# HexBoard.net
KiCad netlist of a schematic drawn in EAGLE
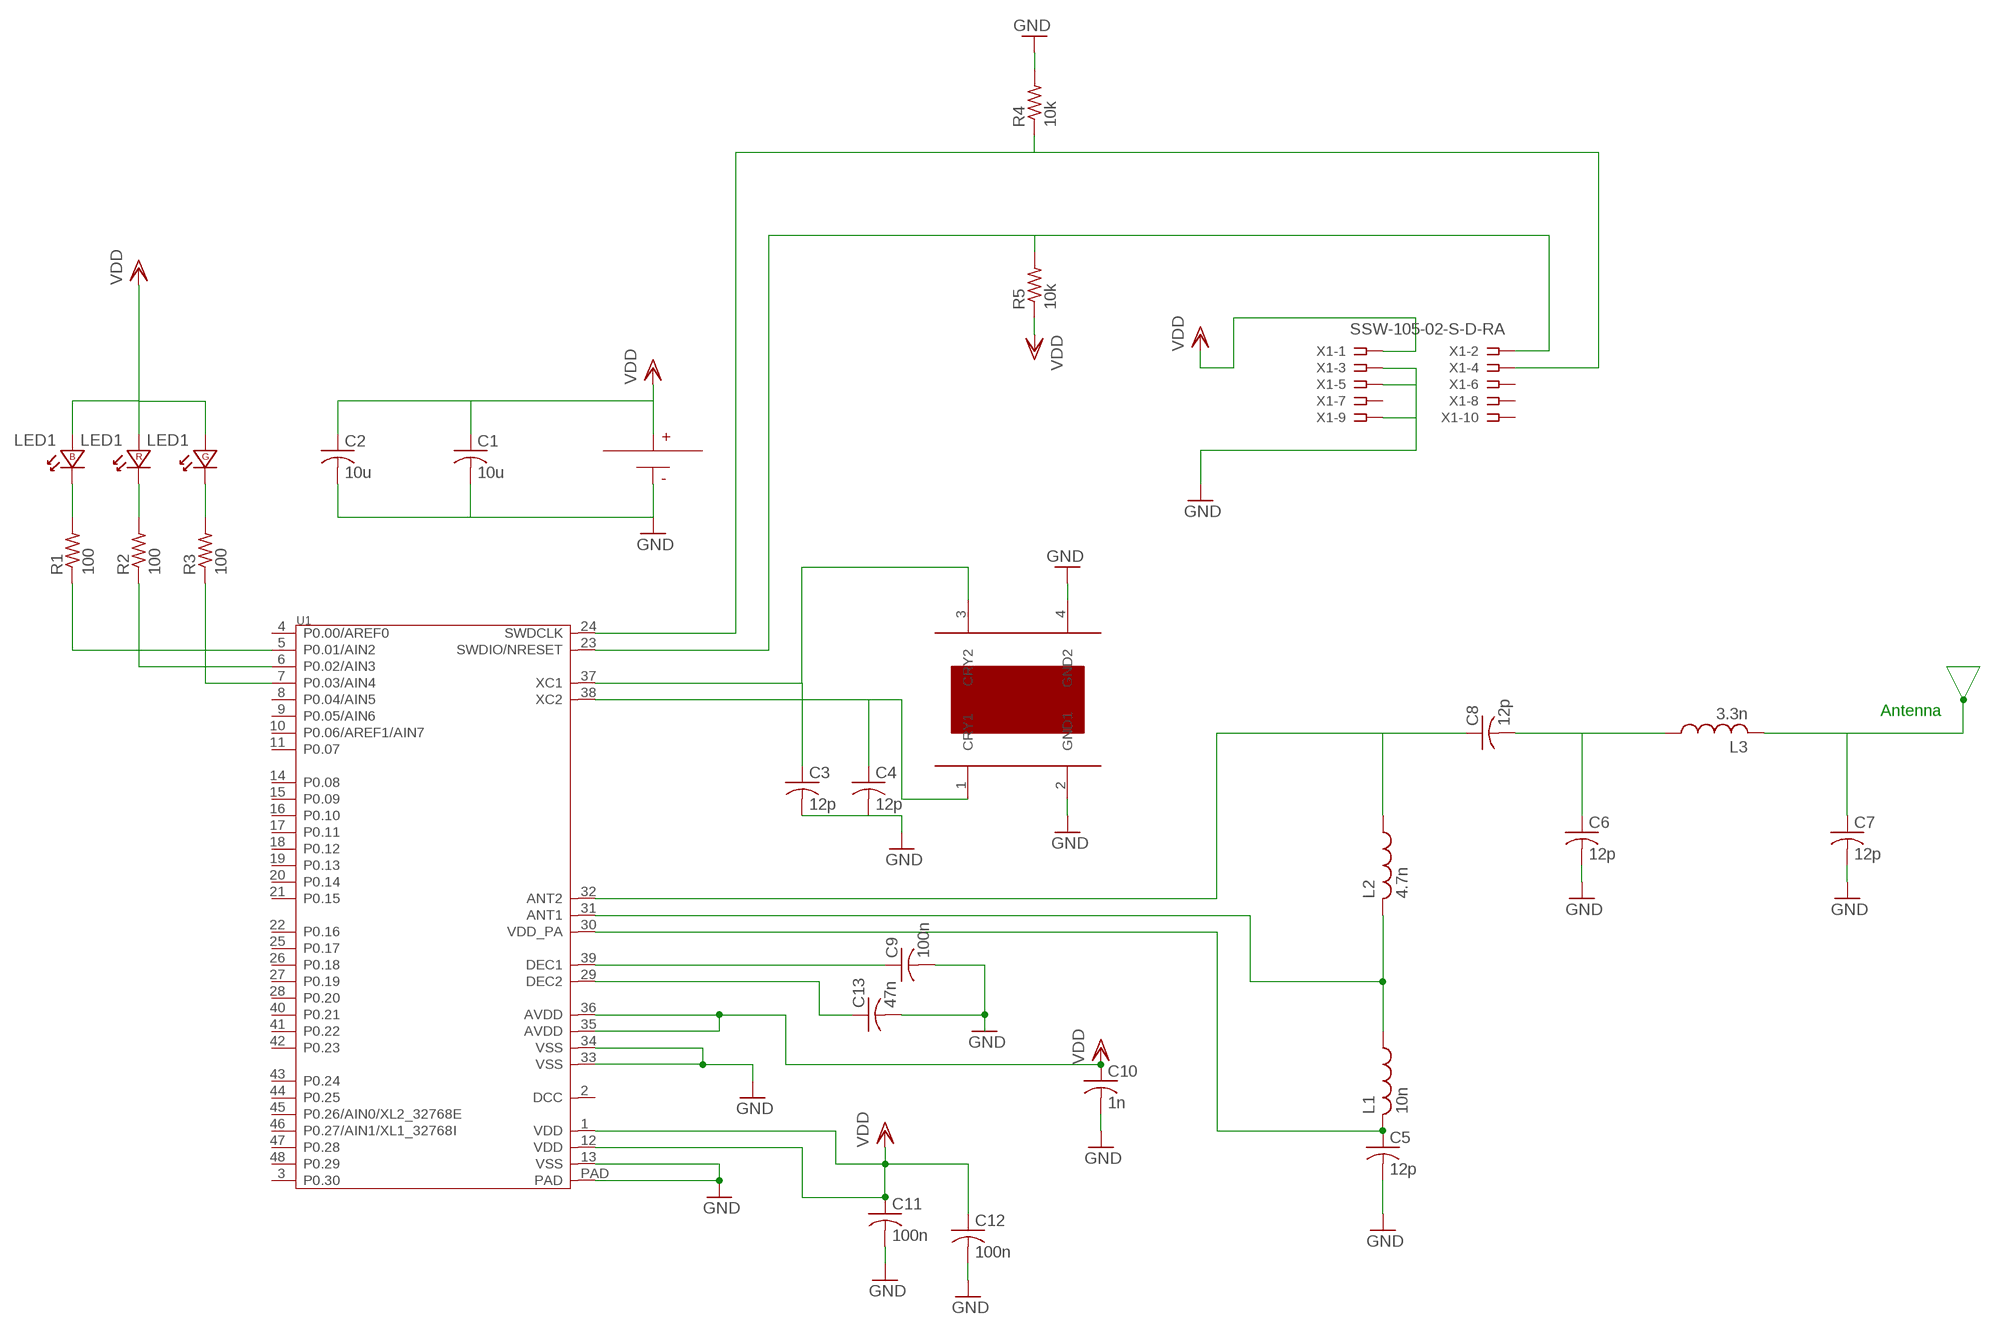
[diagram p0: schematic, sheet 1]

(export (version "E")
  (design (tool "Eeschema 10.0.6"))
  (components
    (comp (ref "B1")
      (value "CON-COINCEL-HOLDER-KEYSTONE-3012TR")
      (footprint "eagle-import:16MM-COINCELL-KEYSTONE")
      (libsource (lib "eagle-import") (part "CON-COINCEL-HOLDER-KEYSTONE-3012TR"))
    )
    (comp (ref "C1")
      (value "10u")
      (footprint "eagle-import:C0805K")
      (libsource (lib "eagle-import") (part "C-USC0805K"))
    )
    (comp (ref "C2")
      (value "10u")
      (footprint "eagle-import:C0805K")
      (libsource (lib "eagle-import") (part "C-USC0805K"))
    )
    (comp (ref "C3")
      (value "12p")
      (footprint "eagle-import:C0402")
      (libsource (lib "eagle-import") (part "C-USC0402"))
    )
    (comp (ref "C4")
      (value "12p")
      (footprint "eagle-import:C0402")
      (libsource (lib "eagle-import") (part "C-USC0402"))
    )
    (comp (ref "C5")
      (value "12p")
      (footprint "eagle-import:C0402")
      (libsource (lib "eagle-import") (part "C-USC0402"))
    )
    (comp (ref "C6")
      (value "12p")
      (footprint "eagle-import:C0402")
      (libsource (lib "eagle-import") (part "C-USC0402"))
    )
    (comp (ref "C7")
      (value "12p")
      (footprint "eagle-import:C0402")
      (libsource (lib "eagle-import") (part "C-USC0402"))
    )
    (comp (ref "C8")
      (value "12p")
      (footprint "eagle-import:C0402")
      (libsource (lib "eagle-import") (part "C-USC0402"))
    )
    (comp (ref "C9")
      (value "100n")
      (footprint "eagle-import:C0402")
      (libsource (lib "eagle-import") (part "C-USC0402"))
    )
    (comp (ref "C10")
      (value "1n")
      (footprint "eagle-import:C0402")
      (libsource (lib "eagle-import") (part "C-USC0402"))
    )
    (comp (ref "C11")
      (value "100n")
      (footprint "eagle-import:C0402")
      (libsource (lib "eagle-import") (part "C-USC0402"))
    )
    (comp (ref "C12")
      (value "100n")
      (footprint "eagle-import:C0402")
      (libsource (lib "eagle-import") (part "C-USC0402"))
    )
    (comp (ref "C13")
      (value "47n")
      (footprint "eagle-import:C0603K")
      (libsource (lib "eagle-import") (part "C-USC0603K"))
    )
    (comp (ref "L1")
      (value "10n")
      (footprint "eagle-import:CHIP_INDUCTOR")
      (libsource (lib "eagle-import") (part "402_CHIP_INDUCTOR"))
    )
    (comp (ref "L2")
      (value "4.7n")
      (footprint "eagle-import:CHIP_INDUCTOR")
      (libsource (lib "eagle-import") (part "402_CHIP_INDUCTOR"))
    )
    (comp (ref "L3")
      (value "3.3n")
      (footprint "eagle-import:CHIP_INDUCTOR")
      (libsource (lib "eagle-import") (part "402_CHIP_INDUCTOR"))
    )
    (comp (ref "LED1")
      (value "LED-RGB-SEPARATE-3528")
      (footprint "eagle-import:LED-3528")
      (libsource (lib "eagle-import") (part "LED-RGB-SEPARATE-3528"))
    )
    (comp (ref "R1")
      (value "100")
      (footprint "eagle-import:R0402")
      (libsource (lib "eagle-import") (part "R-US_R0402"))
    )
    (comp (ref "R2")
      (value "100")
      (footprint "eagle-import:R0402")
      (libsource (lib "eagle-import") (part "R-US_R0402"))
    )
    (comp (ref "R3")
      (value "100")
      (footprint "eagle-import:R0402")
      (libsource (lib "eagle-import") (part "R-US_R0402"))
    )
    (comp (ref "R4")
      (value "10k")
      (footprint "eagle-import:R0402")
      (libsource (lib "eagle-import") (part "R-US_R0402"))
    )
    (comp (ref "R5")
      (value "10k")
      (footprint "eagle-import:R0402")
      (libsource (lib "eagle-import") (part "R-US_R0402"))
    )
    (comp (ref "U$1")
      (value "TXC-CRYSTAL")
      (footprint "eagle-import:TXC_CRYSTAL")
      (libsource (lib "eagle-import") (part "TXC-CRYSTAL"))
    )
    (comp (ref "U1")
      (value "NRF51822")
      (footprint "eagle-import:QFN48-6X6MM")
      (libsource (lib "eagle-import") (part "NRF51822"))
    )
    (comp (ref "X1")
      (value "SSW-105-02-S-D-RA")
      (footprint "eagle-import:TSW-105-02-S-D-RA")
      (libsource (lib "eagle-import") (part "SSW-105-02-S-D-RA"))
    )
  )
  (nets
    (net (code "1") (name "GND") (class "Default")
      (node (ref "B1") (pin "NEG") (pinfunction "NEG_NEG") (pintype "power_in"))
      (node (ref "C1") (pin "2") (pinfunction "2_2") (pintype "passive"))
      (node (ref "C10") (pin "2") (pinfunction "2_2") (pintype "passive"))
      (node (ref "C11") (pin "2") (pinfunction "2_2") (pintype "passive"))
      (node (ref "C12") (pin "2") (pinfunction "2_2") (pintype "passive"))
      (node (ref "C13") (pin "2") (pinfunction "2_2") (pintype "passive"))
      (node (ref "C2") (pin "2") (pinfunction "2_2") (pintype "passive"))
      (node (ref "C3") (pin "2") (pinfunction "2_2") (pintype "passive"))
      (node (ref "C4") (pin "2") (pinfunction "2_2") (pintype "passive"))
      (node (ref "C5") (pin "2") (pinfunction "2_2") (pintype "passive"))
      (node (ref "C6") (pin "2") (pinfunction "2_2") (pintype "passive"))
      (node (ref "C7") (pin "2") (pinfunction "2_2") (pintype "passive"))
      (node (ref "C9") (pin "2") (pinfunction "2_2") (pintype "passive"))
      (node (ref "R4") (pin "2") (pinfunction "2_2") (pintype "passive"))
      (node (ref "U$1") (pin "2") (pinfunction "GND1_2") (pintype "bidirectional"))
      (node (ref "U$1") (pin "4") (pinfunction "GND2_4") (pintype "bidirectional"))
      (node (ref "U1") (pin "13") (pinfunction "VSS_13") (pintype "bidirectional"))
      (node (ref "U1") (pin "33") (pinfunction "VSS_33") (pintype "bidirectional"))
      (node (ref "U1") (pin "34") (pinfunction "VSS_34") (pintype "bidirectional"))
      (node (ref "U1") (pin "PAD") (pinfunction "PAD_PAD") (pintype "bidirectional"))
      (node (ref "X1") (pin "3") (pinfunction "1_3") (pintype "passive"))
      (node (ref "X1") (pin "5") (pinfunction "1_5") (pintype "passive"))
      (node (ref "X1") (pin "9") (pinfunction "1_9") (pintype "passive"))
    )
    (net (code "2") (name "Net-(C6-Pad1)") (class "Default")
      (node (ref "C6") (pin "1") (pinfunction "1_1") (pintype "passive"))
      (node (ref "C8") (pin "2") (pinfunction "2_2") (pintype "passive"))
      (node (ref "L3") (pin "1") (pinfunction "1_1") (pintype "passive"))
    )
    (net (code "3") (name "Net-(C7-Pad1)") (class "Default")
      (node (ref "C7") (pin "1") (pinfunction "1_1") (pintype "passive"))
      (node (ref "L3") (pin "2") (pinfunction "2_2") (pintype "passive"))
    )
    (net (code "4") (name "Net-(LED1A-K)") (class "Default")
      (node (ref "LED1") (pin "6") (pinfunction "K_6") (pintype "passive"))
      (node (ref "R1") (pin "2") (pinfunction "2_2") (pintype "passive"))
    )
    (net (code "5") (name "Net-(LED1B-K)") (class "Default")
      (node (ref "LED1") (pin "4") (pinfunction "K_4") (pintype "passive"))
      (node (ref "R3") (pin "2") (pinfunction "2_2") (pintype "passive"))
    )
    (net (code "6") (name "Net-(LED1C-K)") (class "Default")
      (node (ref "LED1") (pin "5") (pinfunction "K_5") (pintype "passive"))
      (node (ref "R2") (pin "2") (pinfunction "2_2") (pintype "passive"))
    )
    (net (code "7") (name "Net-(U$1-CRY1)") (class "Default")
      (node (ref "C4") (pin "1") (pinfunction "1_1") (pintype "passive"))
      (node (ref "U$1") (pin "1") (pinfunction "CRY1_1") (pintype "bidirectional"))
      (node (ref "U1") (pin "38") (pinfunction "XC2_38") (pintype "bidirectional"))
    )
    (net (code "8") (name "Net-(U$1-CRY2)") (class "Default")
      (node (ref "C3") (pin "1") (pinfunction "1_1") (pintype "passive"))
      (node (ref "U$1") (pin "3") (pinfunction "CRY2_3") (pintype "bidirectional"))
      (node (ref "U1") (pin "37") (pinfunction "XC1_37") (pintype "bidirectional"))
    )
    (net (code "9") (name "Net-(U1-ANT1)") (class "Default")
      (node (ref "L1") (pin "1") (pinfunction "1_1") (pintype "passive"))
      (node (ref "L2") (pin "2") (pinfunction "2_2") (pintype "passive"))
      (node (ref "U1") (pin "31") (pinfunction "ANT1_31") (pintype "bidirectional"))
    )
    (net (code "10") (name "Net-(U1-ANT2)") (class "Default")
      (node (ref "C8") (pin "1") (pinfunction "1_1") (pintype "passive"))
      (node (ref "L2") (pin "1") (pinfunction "1_1") (pintype "passive"))
      (node (ref "U1") (pin "32") (pinfunction "ANT2_32") (pintype "bidirectional"))
    )
    (net (code "11") (name "Net-(U1-DEC1)") (class "Default")
      (node (ref "C9") (pin "1") (pinfunction "1_1") (pintype "passive"))
      (node (ref "U1") (pin "39") (pinfunction "DEC1_39") (pintype "bidirectional"))
    )
    (net (code "12") (name "Net-(U1-DEC2)") (class "Default")
      (node (ref "C13") (pin "1") (pinfunction "1_1") (pintype "passive"))
      (node (ref "U1") (pin "29") (pinfunction "DEC2_29") (pintype "bidirectional"))
    )
    (net (code "13") (name "Net-(U1-P0.01{slash}AIN2)") (class "Default")
      (node (ref "R1") (pin "1") (pinfunction "1_1") (pintype "passive"))
      (node (ref "U1") (pin "5") (pinfunction "P0.01/AIN2_5") (pintype "bidirectional"))
    )
    (net (code "14") (name "Net-(U1-P0.02{slash}AIN3)") (class "Default")
      (node (ref "R2") (pin "1") (pinfunction "1_1") (pintype "passive"))
      (node (ref "U1") (pin "6") (pinfunction "P0.02/AIN3_6") (pintype "bidirectional"))
    )
    (net (code "15") (name "Net-(U1-P0.03{slash}AIN4)") (class "Default")
      (node (ref "R3") (pin "1") (pinfunction "1_1") (pintype "passive"))
      (node (ref "U1") (pin "7") (pinfunction "P0.03/AIN4_7") (pintype "bidirectional"))
    )
    (net (code "16") (name "Net-(U1-SWDCLK)") (class "Default")
      (node (ref "R4") (pin "1") (pinfunction "1_1") (pintype "passive"))
      (node (ref "U1") (pin "24") (pinfunction "SWDCLK_24") (pintype "bidirectional"))
      (node (ref "X1") (pin "4") (pinfunction "1_4") (pintype "passive"))
    )
    (net (code "17") (name "Net-(U1-SWDIO{slash}NRESET)") (class "Default")
      (node (ref "R5") (pin "2") (pinfunction "2_2") (pintype "passive"))
      (node (ref "U1") (pin "23") (pinfunction "SWDIO/NRESET_23") (pintype "bidirectional"))
      (node (ref "X1") (pin "2") (pinfunction "1_2") (pintype "passive"))
    )
    (net (code "18") (name "Net-(U1-VDD_PA)") (class "Default")
      (node (ref "C5") (pin "1") (pinfunction "1_1") (pintype "passive"))
      (node (ref "L1") (pin "2") (pinfunction "2_2") (pintype "passive"))
      (node (ref "U1") (pin "30") (pinfunction "VDD_PA_30") (pintype "bidirectional"))
    )
    (net (code "19") (name "VDD") (class "Default")
      (node (ref "B1") (pin "POS@1") (pinfunction "POS_POS@1") (pintype "power_in"))
      (node (ref "B1") (pin "POS@2") (pinfunction "POS_POS@2") (pintype "power_in"))
      (node (ref "C1") (pin "1") (pinfunction "1_1") (pintype "passive"))
      (node (ref "C10") (pin "1") (pinfunction "1_1") (pintype "passive"))
      (node (ref "C11") (pin "1") (pinfunction "1_1") (pintype "passive"))
      (node (ref "C12") (pin "1") (pinfunction "1_1") (pintype "passive"))
      (node (ref "C2") (pin "1") (pinfunction "1_1") (pintype "passive"))
      (node (ref "LED1") (pin "1") (pinfunction "A_1") (pintype "passive"))
      (node (ref "LED1") (pin "2") (pinfunction "A_2") (pintype "passive"))
      (node (ref "LED1") (pin "3") (pinfunction "A_3") (pintype "passive"))
      (node (ref "R5") (pin "1") (pinfunction "1_1") (pintype "passive"))
      (node (ref "U1") (pin "1") (pinfunction "VDD_1") (pintype "bidirectional"))
      (node (ref "U1") (pin "12") (pinfunction "VDD_12") (pintype "bidirectional"))
      (node (ref "U1") (pin "35") (pinfunction "AVDD_35") (pintype "bidirectional"))
      (node (ref "U1") (pin "36") (pinfunction "AVDD_36") (pintype "bidirectional"))
      (node (ref "X1") (pin "1") (pinfunction "1_1") (pintype "passive"))
    )
    (net (code "20") (name "unconnected-(U1-DCC-Pad2)") (class "Default")
      (node (ref "U1") (pin "2") (pinfunction "DCC_2") (pintype "bidirectional"))
    )
    (net (code "21") (name "unconnected-(U1-P0.00{slash}AREF0-Pad4)") (class "Default")
      (node (ref "U1") (pin "4") (pinfunction "P0.00/AREF0_4") (pintype "bidirectional"))
    )
    (net (code "22") (name "unconnected-(U1-P0.04{slash}AIN5-Pad8)") (class "Default")
      (node (ref "U1") (pin "8") (pinfunction "P0.04/AIN5_8") (pintype "bidirectional"))
    )
    (net (code "23") (name "unconnected-(U1-P0.05{slash}AIN6-Pad9)") (class "Default")
      (node (ref "U1") (pin "9") (pinfunction "P0.05/AIN6_9") (pintype "bidirectional"))
    )
    (net (code "24") (name "unconnected-(U1-P0.06{slash}AREF1{slash}AIN7-Pad10)") (class "Default")
      (node (ref "U1") (pin "10") (pinfunction "P0.06/AREF1/AIN7_10") (pintype "bidirectional"))
    )
    (net (code "25") (name "unconnected-(U1-P0.07-Pad11)") (class "Default")
      (node (ref "U1") (pin "11") (pinfunction "P0.07_11") (pintype "bidirectional"))
    )
    (net (code "26") (name "unconnected-(U1-P0.08-Pad14)") (class "Default")
      (node (ref "U1") (pin "14") (pinfunction "P0.08_14") (pintype "bidirectional"))
    )
    (net (code "27") (name "unconnected-(U1-P0.09-Pad15)") (class "Default")
      (node (ref "U1") (pin "15") (pinfunction "P0.09_15") (pintype "bidirectional"))
    )
    (net (code "28") (name "unconnected-(U1-P0.10-Pad16)") (class "Default")
      (node (ref "U1") (pin "16") (pinfunction "P0.10_16") (pintype "bidirectional"))
    )
    (net (code "29") (name "unconnected-(U1-P0.11-Pad17)") (class "Default")
      (node (ref "U1") (pin "17") (pinfunction "P0.11_17") (pintype "bidirectional"))
    )
    (net (code "30") (name "unconnected-(U1-P0.12-Pad18)") (class "Default")
      (node (ref "U1") (pin "18") (pinfunction "P0.12_18") (pintype "bidirectional"))
    )
    (net (code "31") (name "unconnected-(U1-P0.13-Pad19)") (class "Default")
      (node (ref "U1") (pin "19") (pinfunction "P0.13_19") (pintype "bidirectional"))
    )
    (net (code "32") (name "unconnected-(U1-P0.14-Pad20)") (class "Default")
      (node (ref "U1") (pin "20") (pinfunction "P0.14_20") (pintype "bidirectional"))
    )
    (net (code "33") (name "unconnected-(U1-P0.15-Pad21)") (class "Default")
      (node (ref "U1") (pin "21") (pinfunction "P0.15_21") (pintype "bidirectional"))
    )
    (net (code "34") (name "unconnected-(U1-P0.16-Pad22)") (class "Default")
      (node (ref "U1") (pin "22") (pinfunction "P0.16_22") (pintype "bidirectional"))
    )
    (net (code "35") (name "unconnected-(U1-P0.17-Pad25)") (class "Default")
      (node (ref "U1") (pin "25") (pinfunction "P0.17_25") (pintype "bidirectional"))
    )
    (net (code "36") (name "unconnected-(U1-P0.18-Pad26)") (class "Default")
      (node (ref "U1") (pin "26") (pinfunction "P0.18_26") (pintype "bidirectional"))
    )
    (net (code "37") (name "unconnected-(U1-P0.19-Pad27)") (class "Default")
      (node (ref "U1") (pin "27") (pinfunction "P0.19_27") (pintype "bidirectional"))
    )
    (net (code "38") (name "unconnected-(U1-P0.20-Pad28)") (class "Default")
      (node (ref "U1") (pin "28") (pinfunction "P0.20_28") (pintype "bidirectional"))
    )
    (net (code "39") (name "unconnected-(U1-P0.21-Pad40)") (class "Default")
      (node (ref "U1") (pin "40") (pinfunction "P0.21_40") (pintype "bidirectional"))
    )
    (net (code "40") (name "unconnected-(U1-P0.22-Pad41)") (class "Default")
      (node (ref "U1") (pin "41") (pinfunction "P0.22_41") (pintype "bidirectional"))
    )
    (net (code "41") (name "unconnected-(U1-P0.23-Pad42)") (class "Default")
      (node (ref "U1") (pin "42") (pinfunction "P0.23_42") (pintype "bidirectional"))
    )
    (net (code "42") (name "unconnected-(U1-P0.24-Pad43)") (class "Default")
      (node (ref "U1") (pin "43") (pinfunction "P0.24_43") (pintype "bidirectional"))
    )
    (net (code "43") (name "unconnected-(U1-P0.25-Pad44)") (class "Default")
      (node (ref "U1") (pin "44") (pinfunction "P0.25_44") (pintype "bidirectional"))
    )
    (net (code "44") (name "unconnected-(U1-P0.26{slash}AIN0{slash}XL2_32768E-Pad45)") (class "Default")
      (node (ref "U1") (pin "45") (pinfunction "P0.26/AIN0/XL2_32768E_45") (pintype "bidirectional"))
    )
    (net (code "45") (name "unconnected-(U1-P0.27{slash}AIN1{slash}XL1_32768I-Pad46)") (class "Default")
      (node (ref "U1") (pin "46") (pinfunction "P0.27/AIN1/XL1_32768I_46") (pintype "bidirectional"))
    )
    (net (code "46") (name "unconnected-(U1-P0.28-Pad47)") (class "Default")
      (node (ref "U1") (pin "47") (pinfunction "P0.28_47") (pintype "bidirectional"))
    )
    (net (code "47") (name "unconnected-(U1-P0.29-Pad48)") (class "Default")
      (node (ref "U1") (pin "48") (pinfunction "P0.29_48") (pintype "bidirectional"))
    )
    (net (code "48") (name "unconnected-(U1-P0.30-Pad3)") (class "Default")
      (node (ref "U1") (pin "3") (pinfunction "P0.30_3") (pintype "bidirectional"))
    )
    (net (code "49") (name "unconnected-(X1B-1-Pad10)") (class "Default")
      (node (ref "X1") (pin "10") (pinfunction "1_10") (pintype "passive"))
    )
    (net (code "50") (name "unconnected-(X1G-1-Pad6)") (class "Default")
      (node (ref "X1") (pin "6") (pinfunction "1_6") (pintype "passive"))
    )
    (net (code "51") (name "unconnected-(X1H-1-Pad7)") (class "Default")
      (node (ref "X1") (pin "7") (pinfunction "1_7") (pintype "passive"))
    )
    (net (code "52") (name "unconnected-(X1I-1-Pad8)") (class "Default")
      (node (ref "X1") (pin "8") (pinfunction "1_8") (pintype "passive"))
    )
  )
)
